# Pathfinder.net
KiCad netlist of a schematic drawn in Altium Designer
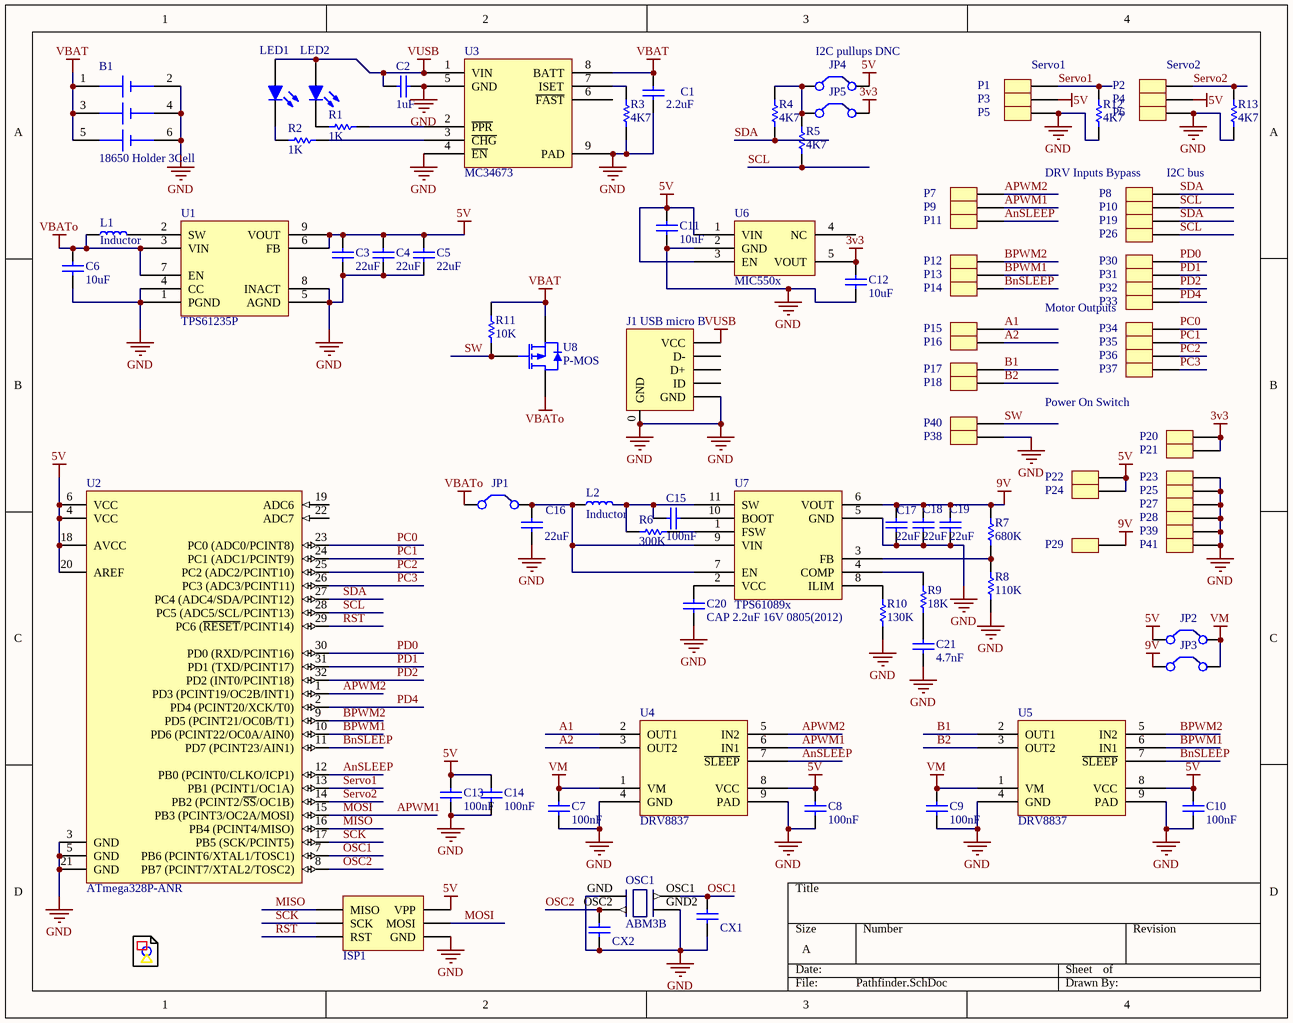
[diagram p0: Pathfinder.SchDoc]

(export (version "E")
  (design (tool "Eeschema 10.0.6"))
  (components
    (comp (ref "*") (value "Logo") (footprint "Zap Cloud") (libsource (lib "DennyLogo") (part "Logo")))
    (comp (ref "B1")
      (value "18650 Holder 3Cell")
      (footprint "18650-3Cell")
      (description "BK-18650-PC6")
      (libsource (lib "Pathfinder_lib") (part "BK18650-3Cell"))
    )
    (comp (ref "C1")
      (value "2.2uF")
      (footprint "CAPC0805(2012)100_L")
      (description "CAP 2.2uF 16V ±10% 0805 (2012 Metric) Thickness 1mm SMD")
      (fields (field (name "TOLERANCE") "Â±10%"))
      (libsource (lib "Altium Content Vault") (part "CAP"))
    )
    (comp (ref "C2")
      (value "1uF")
      (footprint "CAPC0805(2012)100_L")
      (description "CAP 1uF 16V ±20% 0805 (2012 Metric) Thickness 1mm SMD")
      (fields (field (name "TOLERANCE") "Â±20%"))
      (libsource (lib "Altium Content Vault") (part "CAP"))
    )
    (comp (ref "C3")
      (value "22uF")
      (footprint "CAPC0805(2012)100_L")
      (description "CAP 22uF 10V ±20% 0805 (2012 Metric) Thickness 1mm SMD")
      (fields (field (name "TOLERANCE") "Â±20%"))
      (libsource (lib "Altium Content Vault") (part "CAP"))
    )
    (comp (ref "C4")
      (value "22uF")
      (footprint "CAPC0805(2012)100_L")
      (description "CAP 22uF 10V ±20% 0805 (2012 Metric) Thickness 1mm SMD")
      (fields (field (name "TOLERANCE") "Â±20%"))
      (libsource (lib "Altium Content Vault") (part "CAP"))
    )
    (comp (ref "C5")
      (value "22uF")
      (footprint "CAPC0805(2012)100_L")
      (description "CAP 22uF 10V ±20% 0805 (2012 Metric) Thickness 1mm SMD")
      (fields (field (name "TOLERANCE") "Â±20%"))
      (libsource (lib "Altium Content Vault") (part "CAP"))
    )
    (comp (ref "C6")
      (value "10uF")
      (footprint "CAPC0805(2012)145_M")
      (description "CAP 10uF 10V -20% to +80% 0805 (2012 Metric) Thickness 1.45mm SMD")
      (fields (field (name "TOLERANCE") "-20% to +80%"))
      (libsource (lib "Altium Content Vault") (part "CAP"))
    )
    (comp (ref "C7")
      (value "100nF")
      (footprint "CAPC0805(2012)100_M")
      (description "CAP 100nF 10V ±10% 0805 (2012 Metric) Thickness 1mm SMD")
      (fields (field (name "TOLERANCE") "Â±10%"))
      (libsource (lib "Altium Content Vault") (part "CAP"))
    )
    (comp (ref "C8")
      (value "100nF")
      (footprint "CAPC0805(2012)100_M")
      (description "CAP 100nF 10V ±10% 0805 (2012 Metric) Thickness 1mm SMD")
      (fields (field (name "TOLERANCE") "Â±10%"))
      (libsource (lib "Altium Content Vault") (part "CAP"))
    )
    (comp (ref "C9")
      (value "100nF")
      (footprint "CAPC0805(2012)100_M")
      (description "CAP 100nF 10V ±10% 0805 (2012 Metric) Thickness 1mm SMD")
      (fields (field (name "TOLERANCE") "Â±10%"))
      (libsource (lib "Altium Content Vault") (part "CAP"))
    )
    (comp (ref "C10")
      (value "100nF")
      (footprint "CAPC0805(2012)100_M")
      (description "CAP 100nF 10V ±10% 0805 (2012 Metric) Thickness 1mm SMD")
      (fields (field (name "TOLERANCE") "Â±10%"))
      (libsource (lib "Altium Content Vault") (part "CAP"))
    )
    (comp (ref "C11")
      (value "10uF")
      (footprint "CAPC0805(2012)145_M")
      (description "CAP 10uF 10V -20% to +80% 0805 (2012 Metric) Thickness 1.45mm SMD")
      (fields (field (name "TOLERANCE") "-20% to +80%"))
      (libsource (lib "Altium Content Vault") (part "CAP"))
    )
    (comp (ref "C12")
      (value "10uF")
      (footprint "CAPC0805(2012)145_M")
      (description "CAP 10uF 10V -20% to +80% 0805 (2012 Metric) Thickness 1.45mm SMD")
      (fields (field (name "TOLERANCE") "-20% to +80%"))
      (libsource (lib "Altium Content Vault") (part "CAP"))
    )
    (comp (ref "C13")
      (value "100nF")
      (footprint "CAPC0805(2012)100_M")
      (description "CAP 100nF 10V ±10% 0805 (2012 Metric) Thickness 1mm SMD")
      (fields (field (name "TOLERANCE") "Â±10%"))
      (libsource (lib "Altium Content Vault") (part "CAP"))
    )
    (comp (ref "C14")
      (value "100nF")
      (footprint "CAPC0805(2012)100_M")
      (description "CAP 100nF 10V ±10% 0805 (2012 Metric) Thickness 1mm SMD")
      (fields (field (name "TOLERANCE") "Â±10%"))
      (libsource (lib "Altium Content Vault") (part "CAP"))
    )
    (comp (ref "C15")
      (value "100nF")
      (footprint "CAPC0805(2012)100_M")
      (description "CAP 100nF 10V ±10% 0805 (2012 Metric) Thickness 1mm SMD")
      (fields (field (name "TOLERANCE") "Â±10%"))
      (libsource (lib "Altium Content Vault") (part "CAP"))
    )
    (comp (ref "C16")
      (value "22uF")
      (footprint "CAPC0805(2012)100_L")
      (description "CAP 22uF 10V ±20% 0805 (2012 Metric) Thickness 1mm SMD")
      (fields (field (name "TOLERANCE") "Â±20%"))
      (libsource (lib "Altium Content Vault") (part "CAP"))
    )
    (comp (ref "C17")
      (value "22uF")
      (footprint "CAPC0805(2012)100_L")
      (description "CAP 22uF 10V ±20% 0805 (2012 Metric) Thickness 1mm SMD")
      (fields (field (name "TOLERANCE") "Â±20%"))
      (libsource (lib "Altium Content Vault") (part "CAP"))
    )
    (comp (ref "C18")
      (value "22uF")
      (footprint "CAPC0805(2012)100_L")
      (description "CAP 22uF 10V ±20% 0805 (2012 Metric) Thickness 1mm SMD")
      (fields (field (name "TOLERANCE") "Â±20%"))
      (libsource (lib "Altium Content Vault") (part "CAP"))
    )
    (comp (ref "C19")
      (value "22uF")
      (footprint "CAPC0805(2012)100_L")
      (description "CAP 22uF 10V ±20% 0805 (2012 Metric) Thickness 1mm SMD")
      (fields (field (name "TOLERANCE") "Â±20%"))
      (libsource (lib "Altium Content Vault") (part "CAP"))
    )
    (comp (ref "C20")
      (value "CAP 2.2uF 16V 0805(2012)")
      (footprint "CAPC0805(2012)145_L")
      (description "CAP 2.2uF 16V ±10% 0805 (2012 Metric) Thickness 1.45mm SMD")
      (fields (field (name "TOLERANCE") "Â±10%"))
      (libsource (lib "Altium Content Vault") (part "CAP"))
    )
    (comp (ref "C21")
      (value "4.7nF")
      (footprint "CAPC0805(2012)145_N")
      (description "CAP 4.7nF 16V ±1% 0805 (2012 Metric) Thickness 1.45mm SMD")
      (fields (field (name "TOLERANCE") "Â±1%"))
      (libsource (lib "Altium Content Vault") (part "CAP"))
    )
    (comp (ref "CX1")
      (value "CAP 22pF 10V 0603(1608)")
      (footprint "CAPC0603(1608)100_M")
      (description "CAP 22pF 10V ±0.5pF 0603 (1608 Metric) Thickness 1mm SMD")
      (fields (field (name "TOLERANCE") "±0.5pF"))
      (libsource (lib "Altium Content Vault") (part "CMP-1035-00798-1"))
    )
    (comp (ref "CX2")
      (value "CAP 22pF 10V 0603(1608)")
      (footprint "CAPC0603(1608)100_M")
      (description "CAP 22pF 10V ±0.5pF 0603 (1608 Metric) Thickness 1mm SMD")
      (fields (field (name "TOLERANCE") "±0.5pF"))
      (libsource (lib "Altium Content Vault") (part "CMP-1035-00798-1"))
    )
    (comp (ref "ISP1")
      (value "AVRISP")
      (footprint "2x3 100mil Header")
      (description "AVR ISP connection")
      (libsource (lib "Denny") (part "AVRISP"))
    )
    (comp (ref "J1")
      (value "USB micro B")
      (footprint "USB Micro SMD")
      (description "Micro USB connector")
      (libsource (lib "SolarCar") (part "Micro-USB"))
    )
    (comp (ref "JP1")
      (value "SolderJumper")
      (footprint "bridge")
      (description "Solder Configuration Jumper")
      (fields (field (name "PUBLISHER") "Altium Limited"))
      (libsource (lib "SolarCar") (part "SolderJumper"))
    )
    (comp (ref "JP2")
      (value "SolderJumper")
      (footprint "bridge")
      (description "Solder Configuration Jumper")
      (fields (field (name "PUBLISHER") "Altium Limited"))
      (libsource (lib "SolarCar") (part "SolderJumper"))
    )
    (comp (ref "JP3")
      (value "SolderJumper")
      (footprint "bridge")
      (description "Solder Configuration Jumper")
      (fields (field (name "PUBLISHER") "Altium Limited"))
      (libsource (lib "SolarCar") (part "SolderJumper"))
    )
    (comp (ref "JP4")
      (value "SolderJumper")
      (footprint "bridge")
      (description "Solder Configuration Jumper")
      (fields (field (name "PUBLISHER") "Altium Limited"))
      (libsource (lib "SolarCar") (part "SolderJumper"))
    )
    (comp (ref "JP5")
      (value "SolderJumper")
      (footprint "bridge")
      (description "Solder Configuration Jumper")
      (fields (field (name "PUBLISHER") "Altium Limited"))
      (libsource (lib "SolarCar") (part "SolderJumper"))
    )
    (comp (ref "L1")
      (value "Inductor")
      (footprint "XAL7030-102ME")
      (description "Generic Inductor")
      (libsource (lib "Pathfinder_lib") (part "Inductor"))
    )
    (comp (ref "L2")
      (value "Inductor")
      (footprint "CDMC8D28NP-1R8MC")
      (description "Generic Inductor")
      (libsource (lib "Pathfinder_lib") (part "Inductor"))
    )
    (comp (ref "LED1")
      (value "LED2")
      (footprint "LED0805")
      (description "Typical RED, GREEN, YELLOW, AMBER GaAs LED")
      (fields (field (name "PUBLISHER") "Altium Limited"))
      (libsource (lib "SolarCar") (part "LED2"))
    )
    (comp (ref "LED2")
      (value "LED2")
      (footprint "LED0805")
      (description "Typical RED, GREEN, YELLOW, AMBER GaAs LED")
      (fields (field (name "PUBLISHER") "Altium Limited"))
      (libsource (lib "SolarCar") (part "LED2"))
    )
    (comp (ref "OSC1") (value "ABM3B") (footprint "ABM3B") (libsource (lib "SolarCar") (part "ABM3B")))
    (comp (ref "P1") (value "SV1") (footprint "Pin 100mil") (libsource (lib "SolarCar") (part "1-Pin")))
    (comp (ref "P2") (value "SV2") (footprint "Pin 100mil") (libsource (lib "SolarCar") (part "1-Pin")))
    (comp (ref "P3") (value "5V") (footprint "Pin 100mil") (libsource (lib "SolarCar") (part "1-Pin")))
    (comp (ref "P4") (value "5V") (footprint "Pin 100mil") (libsource (lib "SolarCar") (part "1-Pin")))
    (comp (ref "P5") (value "GND") (footprint "Pin 100mil") (libsource (lib "SolarCar") (part "1-Pin")))
    (comp (ref "P6") (value "GND") (footprint "Pin 100mil") (libsource (lib "SolarCar") (part "1-Pin")))
    (comp (ref "P7") (value "Ain2") (footprint "Pin 100mil") (libsource (lib "SolarCar") (part "1-Pin")))
    (comp (ref "P8") (value "SDA") (footprint "Pin 100mil") (libsource (lib "SolarCar") (part "1-Pin")))
    (comp (ref "P9") (value "Ain1") (footprint "Pin 100mil") (libsource (lib "SolarCar") (part "1-Pin")))
    (comp (ref "P10") (value "SCL") (footprint "Pin 100mil") (libsource (lib "SolarCar") (part "1-Pin")))
    (comp (ref "P11") (value "ASLP") (footprint "Pin 100mil") (libsource (lib "SolarCar") (part "1-Pin")))
    (comp (ref "P12") (value "Bin2") (footprint "Pin 100mil") (libsource (lib "SolarCar") (part "1-Pin")))
    (comp (ref "P13") (value "Bin1") (footprint "Pin 100mil") (libsource (lib "SolarCar") (part "1-Pin")))
    (comp (ref "P14") (value "BSLP") (footprint "Pin 100mil") (libsource (lib "SolarCar") (part "1-Pin")))
    (comp (ref "P15") (value "AO1") (footprint "Pin 100mil") (libsource (lib "SolarCar") (part "1-Pin")))
    (comp (ref "P16") (value "AO2") (footprint "Pin 100mil") (libsource (lib "SolarCar") (part "1-Pin")))
    (comp (ref "P17") (value "BO1") (footprint "Pin 100mil") (libsource (lib "SolarCar") (part "1-Pin")))
    (comp (ref "P18") (value "BO2") (footprint "Pin 100mil") (libsource (lib "SolarCar") (part "1-Pin")))
    (comp (ref "P19") (value "SDA") (footprint "Pin 100mil") (libsource (lib "SolarCar") (part "1-Pin")))
    (comp (ref "P20") (value "3v3") (footprint "Pin 100mil") (libsource (lib "SolarCar") (part "1-Pin")))
    (comp (ref "P21") (value "3v3") (footprint "Pin 100mil") (libsource (lib "SolarCar") (part "1-Pin")))
    (comp (ref "P22") (value "5V") (footprint "Pin 100mil") (libsource (lib "SolarCar") (part "1-Pin")))
    (comp (ref "P23") (value "GND") (footprint "Pin 100mil") (libsource (lib "SolarCar") (part "1-Pin")))
    (comp (ref "P24") (value "5V") (footprint "Pin 100mil") (libsource (lib "SolarCar") (part "1-Pin")))
    (comp (ref "P25") (value "GND") (footprint "Pin 100mil") (libsource (lib "SolarCar") (part "1-Pin")))
    (comp (ref "P26") (value "SCL") (footprint "Pin 100mil") (libsource (lib "SolarCar") (part "1-Pin")))
    (comp (ref "P27") (value "GND") (footprint "Pin 100mil") (libsource (lib "SolarCar") (part "1-Pin")))
    (comp (ref "P28") (value "GND") (footprint "Pin 100mil") (libsource (lib "SolarCar") (part "1-Pin")))
    (comp (ref "P29") (value "9V") (footprint "Pin 100mil") (libsource (lib "SolarCar") (part "1-Pin")))
    (comp (ref "P30") (value "PD0") (footprint "Pin 100mil") (libsource (lib "SolarCar") (part "1-Pin")))
    (comp (ref "P31") (value "PD1") (footprint "Pin 100mil") (libsource (lib "SolarCar") (part "1-Pin")))
    (comp (ref "P32") (value "PD2") (footprint "Pin 100mil") (libsource (lib "SolarCar") (part "1-Pin")))
    (comp (ref "P33") (value "PD4") (footprint "Pin 100mil") (libsource (lib "SolarCar") (part "1-Pin")))
    (comp (ref "P34") (value "PC0") (footprint "Pin 100mil") (libsource (lib "SolarCar") (part "1-Pin")))
    (comp (ref "P35") (value "PC1") (footprint "Pin 100mil") (libsource (lib "SolarCar") (part "1-Pin")))
    (comp (ref "P36") (value "PC2") (footprint "Pin 100mil") (libsource (lib "SolarCar") (part "1-Pin")))
    (comp (ref "P37") (value "PC3") (footprint "Pin 100mil") (libsource (lib "SolarCar") (part "1-Pin")))
    (comp (ref "P38") (value "SDA") (footprint "Pin 100mil") (libsource (lib "SolarCar") (part "1-Pin")))
    (comp (ref "P39") (value "GND") (footprint "Pin 100mil") (libsource (lib "SolarCar") (part "1-Pin")))
    (comp (ref "P40") (value "SDA") (footprint "Pin 100mil") (libsource (lib "SolarCar") (part "1-Pin")))
    (comp (ref "P41") (value "GND") (footprint "Pin 100mil") (libsource (lib "SolarCar") (part "1-Pin")))
    (comp (ref "R1")
      (value "1K")
      (footprint "RESC0805(2012)_N")
      (description "1K 0.125W 5% 0805 (2012 Metric)  SMD")
      (fields (field (name "POWER") "0.125 W") (field (name "TOLERANCE") "5 %"))
      (libsource (lib "Altium Content Vault") (part "RES"))
    )
    (comp (ref "R2")
      (value "1K")
      (footprint "RESC0805(2012)_N")
      (description "1K 0.125W 5% 0805 (2012 Metric)  SMD")
      (fields (field (name "POWER") "0.125 W") (field (name "TOLERANCE") "5 %"))
      (libsource (lib "Altium Content Vault") (part "RES"))
    )
    (comp (ref "R3")
      (value "4K7")
      (footprint "RESC0805(2012)_N")
      (description "4K7 0.125W 5% 0805 (2012 Metric)  SMD")
      (fields (field (name "POWER") "0.125 W") (field (name "TOLERANCE") "5 %"))
      (libsource (lib "Altium Content Vault") (part "RES"))
    )
    (comp (ref "R4")
      (value "4K7")
      (footprint "RESC0805(2012)_N")
      (description "4K7 0.125W 5% 0805 (2012 Metric)  SMD")
      (fields (field (name "POWER") "0.125 W") (field (name "TOLERANCE") "5 %"))
      (libsource (lib "Altium Content Vault") (part "RES"))
    )
    (comp (ref "R5")
      (value "4K7")
      (footprint "RESC0805(2012)_N")
      (description "4K7 0.125W 5% 0805 (2012 Metric)  SMD")
      (fields (field (name "POWER") "0.125 W") (field (name "TOLERANCE") "5 %"))
      (libsource (lib "Altium Content Vault") (part "RES"))
    )
    (comp (ref "R6")
      (value "300K")
      (footprint "RESC0805(2012)_M")
      (description "300K 0.125W 5% 0805 (2012 Metric)  SMD")
      (fields (field (name "TOLERANCE") "5 %") (field (name "POWER") "0.125 W"))
      (libsource (lib "Altium Content Vault") (part "RES"))
    )
    (comp (ref "R7")
      (value "680K")
      (footprint "RESC0805(2012)_M")
      (description "680K 0.125W 5% 0805 (2012 Metric)  SMD")
      (fields (field (name "POWER") "0.125 W") (field (name "TOLERANCE") "5 %"))
      (libsource (lib "Altium Content Vault") (part "RES"))
    )
    (comp (ref "R8")
      (value "110K")
      (footprint "RESC0805(2012)_M")
      (description "110K 0.125W 5% 0805 (2012 Metric)  SMD")
      (fields (field (name "TOLERANCE") "5 %") (field (name "POWER") "0.125 W"))
      (libsource (lib "Altium Content Vault") (part "RES"))
    )
    (comp (ref "R9")
      (value "18K")
      (footprint "RESC0805(2012)_M")
      (description "18K 0.125W 5% 0805 (2012 Metric)  SMD")
      (fields (field (name "POWER") "0.125 W") (field (name "TOLERANCE") "5 %"))
      (libsource (lib "Altium Content Vault") (part "RES"))
    )
    (comp (ref "R10")
      (value "130K")
      (footprint "RESC0805(2012)_N")
      (description "130K 0.125W 5% 0805 (2012 Metric)  SMD")
      (fields (field (name "TOLERANCE") "5 %") (field (name "POWER") "0.125 W"))
      (libsource (lib "Altium Content Vault") (part "RES"))
    )
    (comp (ref "R11")
      (value "10K")
      (footprint "RESC0603(1608)_N")
      (description "10K 0.1W 5% 0603 (1608 Metric)  SMD")
      (fields (field (name "TOLERANCE") "5 %") (field (name "POWER") "0.1 W"))
      (libsource (lib "Altium Content Vault") (part "RES"))
    )
    (comp (ref "R12")
      (value "4K7")
      (footprint "RESC0805(2012)_N")
      (description "4K7 0.125W 5% 0805 (2012 Metric)  SMD")
      (fields (field (name "POWER") "0.125 W") (field (name "TOLERANCE") "5 %"))
      (libsource (lib "Altium Content Vault") (part "RES"))
    )
    (comp (ref "R13")
      (value "4K7")
      (footprint "RESC0805(2012)_N")
      (description "4K7 0.125W 5% 0805 (2012 Metric)  SMD")
      (fields (field (name "POWER") "0.125 W") (field (name "TOLERANCE") "5 %"))
      (libsource (lib "Altium Content Vault") (part "RES"))
    )
    (comp (ref "U1")
      (value "TPS61235P")
      (footprint "VQFN-HR-TPS61235PRWLR")
      (description "8-A Valley Current Synchronous Boost Converter")
      (libsource (lib "Pathfinder_lib") (part "TPS61235P"))
    )
    (comp (ref "U2")
      (value "ATmega328P-ANR")
      (footprint "32A_M")
      (libsource (lib "Altium Content Vault") (part "CMP-0095-00621-1"))
    )
    (comp (ref "U3")
      (value "MC34673")
      (footprint "UDFN-8 2 x 3 x 0.65")
      (description "1.2A Charger  for Single-cell Li-Ion Batteries")
      (libsource (lib "Pathfinder_lib") (part "MC34673"))
    )
    (comp (ref "U4")
      (value "DRV8837")
      (footprint "WSON-8")
      (description "Low-Voltage H-Bridge Driver")
      (libsource (lib "Pathfinder_lib") (part "DRV8837"))
    )
    (comp (ref "U5")
      (value "DRV8837")
      (footprint "WSON-8")
      (description "Low-Voltage H-Bridge Driver")
      (libsource (lib "Pathfinder_lib") (part "DRV8837"))
    )
    (comp (ref "U6")
      (value "MIC550x")
      (footprint "SOT-23-5")
      (description "MIC550x Regulator")
      (libsource (lib "Denny") (part "MIC550x"))
    )
    (comp (ref "U7")
      (value "TPS61089x")
      (footprint "VQFN-11 2 x 2.5")
      (description "12.6-V, 7-A Fully-Integrated Synchronous Boost Converter")
      (libsource (lib "Pathfinder_lib") (part "TPS61089x"))
    )
    (comp (ref "U8")
      (value "P-MOS")
      (footprint "SOIC-8-MOSFET")
      (description "SI4403CDY-T1")
      (libsource (lib "Pathfinder_lib") (part "SI4403CDY-T1"))
    )
  )
  (nets
    (net (code "1") (name "/A1") (class "Default")
      (node (ref "P15") (pin "0") (pinfunction "0_0") (pintype "passive"))
      (node (ref "U4") (pin "2") (pinfunction "OUT1_2") (pintype "passive"))
    )
    (net (code "2") (name "/A2") (class "Default")
      (node (ref "P16") (pin "0") (pinfunction "0_0") (pintype "passive"))
      (node (ref "U4") (pin "3") (pinfunction "OUT2_3") (pintype "passive"))
    )
    (net (code "3") (name "/APWM1") (class "Default")
      (node (ref "ISP1") (pin "4") (pinfunction "MOSI_4") (pintype "passive"))
      (node (ref "P9") (pin "0") (pinfunction "0_0") (pintype "passive"))
      (node (ref "U2") (pin "15") (pinfunction "PB3_(PCINT3/OC2A/MOSI)_15") (pintype "bidirectional"))
      (node (ref "U4") (pin "6") (pinfunction "IN1_6") (pintype "passive"))
    )
    (net (code "4") (name "/APWM2") (class "Default")
      (node (ref "P7") (pin "0") (pinfunction "0_0") (pintype "passive"))
      (node (ref "U2") (pin "1") (pinfunction "PD3_(PCINT19/OC2B/INT1)_1") (pintype "bidirectional"))
      (node (ref "U4") (pin "5") (pinfunction "IN2_5") (pintype "passive"))
    )
    (net (code "5") (name "/AnSLEEP") (class "Default")
      (node (ref "P11") (pin "0") (pinfunction "0_0") (pintype "passive"))
      (node (ref "U2") (pin "12") (pinfunction "PB0_(PCINT0/CLKO/ICP1)_12") (pintype "bidirectional"))
      (node (ref "U4") (pin "7") (pinfunction "~{SLEEP}_7") (pintype "passive"))
    )
    (net (code "6") (name "/B1") (class "Default")
      (node (ref "P17") (pin "0") (pinfunction "0_0") (pintype "passive"))
      (node (ref "U5") (pin "2") (pinfunction "OUT1_2") (pintype "passive"))
    )
    (net (code "7") (name "/B2") (class "Default")
      (node (ref "P18") (pin "0") (pinfunction "0_0") (pintype "passive"))
      (node (ref "U5") (pin "3") (pinfunction "OUT2_3") (pintype "passive"))
    )
    (net (code "8") (name "/BPWM1") (class "Default")
      (node (ref "P13") (pin "0") (pinfunction "0_0") (pintype "passive"))
      (node (ref "U2") (pin "10") (pinfunction "PD6_(PCINT22/OC0A/AIN0)_10") (pintype "bidirectional"))
      (node (ref "U5") (pin "6") (pinfunction "IN1_6") (pintype "passive"))
    )
    (net (code "9") (name "/BPWM2") (class "Default")
      (node (ref "P12") (pin "0") (pinfunction "0_0") (pintype "passive"))
      (node (ref "U2") (pin "9") (pinfunction "PD5_(PCINT21/OC0B/T1)_9") (pintype "bidirectional"))
      (node (ref "U5") (pin "5") (pinfunction "IN2_5") (pintype "passive"))
    )
    (net (code "10") (name "/BnSLEEP") (class "Default")
      (node (ref "P14") (pin "0") (pinfunction "0_0") (pintype "passive"))
      (node (ref "U2") (pin "11") (pinfunction "PD7_(PCINT23/AIN1)_11") (pintype "bidirectional"))
      (node (ref "U5") (pin "7") (pinfunction "~{SLEEP}_7") (pintype "passive"))
    )
    (net (code "11") (name "/MISO") (class "Default")
      (node (ref "ISP1") (pin "1") (pinfunction "MISO_1") (pintype "passive"))
      (node (ref "U2") (pin "16") (pinfunction "PB4_(PCINT4/MISO)_16") (pintype "bidirectional"))
    )
    (net (code "12") (name "/OSC1") (class "Default")
      (node (ref "CX1") (pin "2") (pinfunction "2_2") (pintype "passive"))
      (node (ref "OSC1") (pin "OSC1") (pinfunction "OSC1_OSC1") (pintype "output"))
      (node (ref "U2") (pin "7") (pinfunction "PB6_(PCINT6/XTAL1/TOSC1)_7") (pintype "bidirectional"))
    )
    (net (code "13") (name "/OSC2") (class "Default")
      (node (ref "CX2") (pin "2") (pinfunction "2_2") (pintype "passive"))
      (node (ref "OSC1") (pin "OSC2") (pinfunction "OSC2_OSC2") (pintype "output"))
      (node (ref "U2") (pin "8") (pinfunction "PB7_(PCINT7/XTAL2/TOSC2)_8") (pintype "bidirectional"))
    )
    (net (code "14") (name "/PC0") (class "Default")
      (node (ref "P34") (pin "0") (pinfunction "0_0") (pintype "passive"))
      (node (ref "U2") (pin "23") (pinfunction "PC0_(ADC0/PCINT8)_23") (pintype "bidirectional"))
    )
    (net (code "15") (name "/PC1") (class "Default")
      (node (ref "P35") (pin "0") (pinfunction "0_0") (pintype "passive"))
      (node (ref "U2") (pin "24") (pinfunction "PC1_(ADC1/PCINT9)_24") (pintype "bidirectional"))
    )
    (net (code "16") (name "/PC2") (class "Default")
      (node (ref "P36") (pin "0") (pinfunction "0_0") (pintype "passive"))
      (node (ref "U2") (pin "25") (pinfunction "PC2_(ADC2/PCINT10)_25") (pintype "bidirectional"))
    )
    (net (code "17") (name "/PC3") (class "Default")
      (node (ref "P37") (pin "0") (pinfunction "0_0") (pintype "passive"))
      (node (ref "U2") (pin "26") (pinfunction "PC3_(ADC3/PCINT11)_26") (pintype "bidirectional"))
    )
    (net (code "18") (name "/PD0") (class "Default")
      (node (ref "P30") (pin "0") (pinfunction "0_0") (pintype "passive"))
      (node (ref "U2") (pin "30") (pinfunction "PD0_(RXD/PCINT16)_30") (pintype "bidirectional"))
    )
    (net (code "19") (name "/PD1") (class "Default")
      (node (ref "P31") (pin "0") (pinfunction "0_0") (pintype "passive"))
      (node (ref "U2") (pin "31") (pinfunction "PD1_(TXD/PCINT17)_31") (pintype "bidirectional"))
    )
    (net (code "20") (name "/PD2") (class "Default")
      (node (ref "P32") (pin "0") (pinfunction "0_0") (pintype "passive"))
      (node (ref "U2") (pin "32") (pinfunction "PD2_(INT0/PCINT18)_32") (pintype "bidirectional"))
    )
    (net (code "21") (name "/PD4") (class "Default")
      (node (ref "P33") (pin "0") (pinfunction "0_0") (pintype "passive"))
      (node (ref "U2") (pin "2") (pinfunction "PD4_(PCINT20/XCK/T0)_2") (pintype "bidirectional"))
    )
    (net (code "22") (name "/RST") (class "Default")
      (node (ref "ISP1") (pin "5") (pinfunction "RST_5") (pintype "passive"))
      (node (ref "U2") (pin "29") (pinfunction "PC6_(~{RESET}/PCINT14)_29") (pintype "bidirectional"))
    )
    (net (code "23") (name "/SCK") (class "Default")
      (node (ref "ISP1") (pin "3") (pinfunction "SCK_3") (pintype "passive"))
      (node (ref "U2") (pin "17") (pinfunction "PB5_(SCK/PCINT5)_17") (pintype "bidirectional"))
    )
    (net (code "24") (name "/SCL") (class "Default")
      (node (ref "P10") (pin "0") (pinfunction "0_0") (pintype "passive"))
      (node (ref "P26") (pin "0") (pinfunction "0_0") (pintype "passive"))
      (node (ref "R5") (pin "1") (pinfunction "1_1") (pintype "passive"))
      (node (ref "U2") (pin "28") (pinfunction "PC5_(ADC5/SCL/PCINT13)_28") (pintype "bidirectional"))
    )
    (net (code "25") (name "/SDA") (class "Default")
      (node (ref "P19") (pin "0") (pinfunction "0_0") (pintype "passive"))
      (node (ref "P8") (pin "0") (pinfunction "0_0") (pintype "passive"))
      (node (ref "R4") (pin "1") (pinfunction "1_1") (pintype "passive"))
      (node (ref "U2") (pin "27") (pinfunction "PC4_(ADC4/SDA/PCINT12)_27") (pintype "bidirectional"))
    )
    (net (code "26") (name "/SW") (class "Default")
      (node (ref "P40") (pin "0") (pinfunction "0_0") (pintype "passive"))
      (node (ref "R11") (pin "1") (pinfunction "1_1") (pintype "passive"))
      (node (ref "U8") (pin "2") (pinfunction "G_2") (pintype "passive"))
    )
    (net (code "27") (name "/Servo1") (class "Default")
      (node (ref "P1") (pin "0") (pinfunction "0_0") (pintype "passive"))
      (node (ref "R12") (pin "2") (pinfunction "2_2") (pintype "passive"))
      (node (ref "U2") (pin "13") (pinfunction "PB1_(PCINT1/OC1A)_13") (pintype "bidirectional"))
    )
    (net (code "28") (name "/Servo2") (class "Default")
      (node (ref "P2") (pin "0") (pinfunction "0_0") (pintype "passive"))
      (node (ref "R13") (pin "2") (pinfunction "2_2") (pintype "passive"))
      (node (ref "U2") (pin "14") (pinfunction "PB2_(PCINT2/~{SS}/OC1B)_14") (pintype "bidirectional"))
    )
    (net (code "29") (name "3v3") (class "Default")
      (node (ref "C12") (pin "2") (pinfunction "2_2") (pintype "passive"))
      (node (ref "JP5") (pin "2") (pinfunction "C2_2") (pintype "passive"))
      (node (ref "P20") (pin "0") (pinfunction "0_0") (pintype "passive"))
      (node (ref "P21") (pin "0") (pinfunction "0_0") (pintype "passive"))
      (node (ref "U6") (pin "5") (pinfunction "VOUT_5") (pintype "passive"))
    )
    (net (code "30") (name "5V") (class "Default")
      (node (ref "C10") (pin "2") (pinfunction "2_2") (pintype "passive"))
      (node (ref "C11") (pin "2") (pinfunction "2_2") (pintype "passive"))
      (node (ref "C13") (pin "2") (pinfunction "2_2") (pintype "passive"))
      (node (ref "C14") (pin "2") (pinfunction "2_2") (pintype "passive"))
      (node (ref "C3") (pin "2") (pinfunction "2_2") (pintype "passive"))
      (node (ref "C4") (pin "2") (pinfunction "2_2") (pintype "passive"))
      (node (ref "C5") (pin "2") (pinfunction "2_2") (pintype "passive"))
      (node (ref "C8") (pin "2") (pinfunction "2_2") (pintype "passive"))
      (node (ref "ISP1") (pin "2") (pinfunction "VPP_2") (pintype "passive"))
      (node (ref "JP2") (pin "1") (pinfunction "C1_1") (pintype "passive"))
      (node (ref "JP4") (pin "2") (pinfunction "C2_2") (pintype "passive"))
      (node (ref "P22") (pin "0") (pinfunction "0_0") (pintype "passive"))
      (node (ref "P24") (pin "0") (pinfunction "0_0") (pintype "passive"))
      (node (ref "P3") (pin "0") (pinfunction "0_0") (pintype "passive"))
      (node (ref "P4") (pin "0") (pinfunction "0_0") (pintype "passive"))
      (node (ref "U1") (pin "6") (pinfunction "FB_6") (pintype "passive"))
      (node (ref "U1") (pin "9") (pinfunction "VOUT_9") (pintype "passive"))
      (node (ref "U2") (pin "18") (pinfunction "AVCC_18") (pintype "power_in"))
      (node (ref "U2") (pin "20") (pinfunction "AREF_20") (pintype "passive"))
      (node (ref "U2") (pin "4") (pinfunction "VCC_4") (pintype "power_in"))
      (node (ref "U2") (pin "6") (pinfunction "VCC_6") (pintype "power_in"))
      (node (ref "U4") (pin "8") (pinfunction "VCC_8") (pintype "passive"))
      (node (ref "U5") (pin "8") (pinfunction "VCC_8") (pintype "passive"))
      (node (ref "U6") (pin "1") (pinfunction "VIN_1") (pintype "passive"))
      (node (ref "U6") (pin "3") (pinfunction "EN_3") (pintype "passive"))
    )
    (net (code "31") (name "9V") (class "Default")
      (node (ref "C17") (pin "2") (pinfunction "2_2") (pintype "passive"))
      (node (ref "C18") (pin "2") (pinfunction "2_2") (pintype "passive"))
      (node (ref "C19") (pin "2") (pinfunction "2_2") (pintype "passive"))
      (node (ref "JP3") (pin "1") (pinfunction "C1_1") (pintype "passive"))
      (node (ref "P29") (pin "0") (pinfunction "0_0") (pintype "passive"))
      (node (ref "R7") (pin "2") (pinfunction "2_2") (pintype "passive"))
      (node (ref "U7") (pin "6") (pinfunction "VOUT_6") (pintype "passive"))
    )
    (net (code "32") (name "GND") (class "Default")
      (node (ref "B1") (pin "2") (pinfunction "2_2") (pintype "passive"))
      (node (ref "B1") (pin "4") (pinfunction "4_4") (pintype "passive"))
      (node (ref "B1") (pin "6") (pinfunction "6_6") (pintype "passive"))
      (node (ref "C1") (pin "1") (pinfunction "1_1") (pintype "passive"))
      (node (ref "C10") (pin "1") (pinfunction "1_1") (pintype "passive"))
      (node (ref "C11") (pin "1") (pinfunction "1_1") (pintype "passive"))
      (node (ref "C12") (pin "1") (pinfunction "1_1") (pintype "passive"))
      (node (ref "C13") (pin "1") (pinfunction "1_1") (pintype "passive"))
      (node (ref "C14") (pin "1") (pinfunction "1_1") (pintype "passive"))
      (node (ref "C16") (pin "1") (pinfunction "1_1") (pintype "passive"))
      (node (ref "C17") (pin "1") (pinfunction "1_1") (pintype "passive"))
      (node (ref "C18") (pin "1") (pinfunction "1_1") (pintype "passive"))
      (node (ref "C19") (pin "1") (pinfunction "1_1") (pintype "passive"))
      (node (ref "C2") (pin "1") (pinfunction "1_1") (pintype "passive"))
      (node (ref "C20") (pin "1") (pinfunction "1_1") (pintype "passive"))
      (node (ref "C21") (pin "1") (pinfunction "1_1") (pintype "passive"))
      (node (ref "C3") (pin "1") (pinfunction "1_1") (pintype "passive"))
      (node (ref "C4") (pin "1") (pinfunction "1_1") (pintype "passive"))
      (node (ref "C5") (pin "1") (pinfunction "1_1") (pintype "passive"))
      (node (ref "C6") (pin "1") (pinfunction "1_1") (pintype "passive"))
      (node (ref "C7") (pin "1") (pinfunction "1_1") (pintype "passive"))
      (node (ref "C8") (pin "1") (pinfunction "1_1") (pintype "passive"))
      (node (ref "C9") (pin "1") (pinfunction "1_1") (pintype "passive"))
      (node (ref "CX1") (pin "1") (pinfunction "1_1") (pintype "passive"))
      (node (ref "CX2") (pin "1") (pinfunction "1_1") (pintype "passive"))
      (node (ref "ISP1") (pin "6") (pinfunction "GND_6") (pintype "passive"))
      (node (ref "J1") (pin "0") (pinfunction "GND_0") (pintype "passive"))
      (node (ref "J1") (pin "5") (pinfunction "GND_5") (pintype "passive"))
      (node (ref "OSC1") (pin "GND") (pinfunction "GND_GND") (pintype "power_in"))
      (node (ref "OSC1") (pin "GND2") (pinfunction "GND_GND2") (pintype "power_in"))
      (node (ref "P23") (pin "0") (pinfunction "0_0") (pintype "passive"))
      (node (ref "P25") (pin "0") (pinfunction "0_0") (pintype "passive"))
      (node (ref "P27") (pin "0") (pinfunction "0_0") (pintype "passive"))
      (node (ref "P28") (pin "0") (pinfunction "0_0") (pintype "passive"))
      (node (ref "P38") (pin "0") (pinfunction "0_0") (pintype "passive"))
      (node (ref "P39") (pin "0") (pinfunction "0_0") (pintype "passive"))
      (node (ref "P41") (pin "0") (pinfunction "0_0") (pintype "passive"))
      (node (ref "P5") (pin "0") (pinfunction "0_0") (pintype "passive"))
      (node (ref "P6") (pin "0") (pinfunction "0_0") (pintype "passive"))
      (node (ref "R10") (pin "1") (pinfunction "1_1") (pintype "passive"))
      (node (ref "R12") (pin "1") (pinfunction "1_1") (pintype "passive"))
      (node (ref "R13") (pin "1") (pinfunction "1_1") (pintype "passive"))
      (node (ref "R3") (pin "1") (pinfunction "1_1") (pintype "passive"))
      (node (ref "R8") (pin "1") (pinfunction "1_1") (pintype "passive"))
      (node (ref "U1") (pin "1") (pinfunction "PGND_1") (pintype "passive"))
      (node (ref "U1") (pin "4") (pinfunction "CC_4") (pintype "passive"))
      (node (ref "U1") (pin "5") (pinfunction "AGND_5") (pintype "passive"))
      (node (ref "U1") (pin "8") (pinfunction "INACT_8") (pintype "passive"))
      (node (ref "U2") (pin "21") (pinfunction "GND_21") (pintype "power_in"))
      (node (ref "U2") (pin "3") (pinfunction "GND_3") (pintype "power_in"))
      (node (ref "U2") (pin "5") (pinfunction "GND_5") (pintype "power_in"))
      (node (ref "U3") (pin "4") (pinfunction "~{EN}_4") (pintype "passive"))
      (node (ref "U3") (pin "5") (pinfunction "GND_5") (pintype "passive"))
      (node (ref "U3") (pin "9") (pinfunction "PAD_9") (pintype "passive"))
      (node (ref "U4") (pin "4") (pinfunction "GND_4") (pintype "passive"))
      (node (ref "U4") (pin "9") (pinfunction "PAD_9") (pintype "passive"))
      (node (ref "U5") (pin "4") (pinfunction "GND_4") (pintype "passive"))
      (node (ref "U5") (pin "9") (pinfunction "PAD_9") (pintype "passive"))
      (node (ref "U6") (pin "2") (pinfunction "GND_2") (pintype "passive"))
      (node (ref "U7") (pin "5") (pinfunction "GND_5") (pintype "passive"))
    )
    (net (code "33") (name "Net-(C21-Pad2)") (class "Default")
      (node (ref "C21") (pin "2") (pinfunction "2_2") (pintype "passive"))
      (node (ref "R9") (pin "1") (pinfunction "1_1") (pintype "passive"))
    )
    (net (code "34") (name "Net-(JP1-C2)") (class "Default")
      (node (ref "C16") (pin "2") (pinfunction "2_2") (pintype "passive"))
      (node (ref "JP1") (pin "2") (pinfunction "C2_2") (pintype "passive"))
      (node (ref "L2") (pin "1") (pinfunction "1_1") (pintype "passive"))
      (node (ref "U7") (pin "7") (pinfunction "EN_7") (pintype "passive"))
      (node (ref "U7") (pin "9") (pinfunction "VIN_9") (pintype "passive"))
    )
    (net (code "35") (name "Net-(JP4-C1)") (class "Default")
      (node (ref "JP4") (pin "1") (pinfunction "C1_1") (pintype "passive"))
      (node (ref "JP5") (pin "1") (pinfunction "C1_1") (pintype "passive"))
      (node (ref "R4") (pin "2") (pinfunction "2_2") (pintype "passive"))
      (node (ref "R5") (pin "2") (pinfunction "2_2") (pintype "passive"))
    )
    (net (code "36") (name "Net-(LED1-K)") (class "Default")
      (node (ref "LED1") (pin "2") (pinfunction "K_2") (pintype "passive"))
      (node (ref "R2") (pin "2") (pinfunction "2_2") (pintype "passive"))
    )
    (net (code "37") (name "Net-(LED2-K)") (class "Default")
      (node (ref "LED2") (pin "2") (pinfunction "K_2") (pintype "passive"))
      (node (ref "R1") (pin "2") (pinfunction "2_2") (pintype "passive"))
    )
    (net (code "38") (name "Net-(U1-SW)") (class "Default")
      (node (ref "L1") (pin "2") (pinfunction "2_2") (pintype "passive"))
      (node (ref "U1") (pin "2") (pinfunction "SW_2") (pintype "passive"))
    )
    (net (code "39") (name "Net-(U3-ISET)") (class "Default")
      (node (ref "R3") (pin "2") (pinfunction "2_2") (pintype "passive"))
      (node (ref "U3") (pin "7") (pinfunction "ISET_7") (pintype "passive"))
    )
    (net (code "40") (name "Net-(U3-~{CHG})") (class "Default")
      (node (ref "R2") (pin "1") (pinfunction "1_1") (pintype "passive"))
      (node (ref "U3") (pin "3") (pinfunction "~{CHG}_3") (pintype "passive"))
    )
    (net (code "41") (name "Net-(U3-~{PPR})") (class "Default")
      (node (ref "R1") (pin "1") (pinfunction "1_1") (pintype "passive"))
      (node (ref "U3") (pin "2") (pinfunction "~{PPR}_2") (pintype "passive"))
    )
    (net (code "42") (name "Net-(U7-BOOT)") (class "Default")
      (node (ref "C15") (pin "1") (pinfunction "1_1") (pintype "passive"))
      (node (ref "U7") (pin "10") (pinfunction "BOOT_10") (pintype "passive"))
    )
    (net (code "43") (name "Net-(U7-COMP)") (class "Default")
      (node (ref "R9") (pin "2") (pinfunction "2_2") (pintype "passive"))
      (node (ref "U7") (pin "4") (pinfunction "COMP_4") (pintype "passive"))
    )
    (net (code "44") (name "Net-(U7-FB)") (class "Default")
      (node (ref "R7") (pin "1") (pinfunction "1_1") (pintype "passive"))
      (node (ref "R8") (pin "2") (pinfunction "2_2") (pintype "passive"))
      (node (ref "U7") (pin "3") (pinfunction "FB_3") (pintype "passive"))
    )
    (net (code "45") (name "Net-(U7-FSW)") (class "Default")
      (node (ref "R6") (pin "1") (pinfunction "1_1") (pintype "passive"))
      (node (ref "U7") (pin "1") (pinfunction "FSW_1") (pintype "passive"))
    )
    (net (code "46") (name "Net-(U7-ILIM)") (class "Default")
      (node (ref "R10") (pin "2") (pinfunction "2_2") (pintype "passive"))
      (node (ref "U7") (pin "8") (pinfunction "ILIM_8") (pintype "passive"))
    )
    (net (code "47") (name "Net-(U7-SW)") (class "Default")
      (node (ref "C15") (pin "2") (pinfunction "2_2") (pintype "passive"))
      (node (ref "L2") (pin "2") (pinfunction "2_2") (pintype "passive"))
      (node (ref "R6") (pin "2") (pinfunction "2_2") (pintype "passive"))
      (node (ref "U7") (pin "11") (pinfunction "SW_11") (pintype "passive"))
    )
    (net (code "48") (name "Net-(U7-VCC)") (class "Default")
      (node (ref "C20") (pin "2") (pinfunction "2_2") (pintype "passive"))
      (node (ref "U7") (pin "2") (pinfunction "VCC_2") (pintype "passive"))
    )
    (net (code "49") (name "VBAT") (class "Default")
      (node (ref "B1") (pin "1") (pinfunction "1_1") (pintype "passive"))
      (node (ref "B1") (pin "3") (pinfunction "3_3") (pintype "passive"))
      (node (ref "B1") (pin "5") (pinfunction "5_5") (pintype "passive"))
      (node (ref "C1") (pin "2") (pinfunction "2_2") (pintype "passive"))
      (node (ref "R11") (pin "2") (pinfunction "2_2") (pintype "passive"))
      (node (ref "U3") (pin "8") (pinfunction "BATT_8") (pintype "passive"))
      (node (ref "U8") (pin "1") (pinfunction "S_1") (pintype "passive"))
    )
    (net (code "50") (name "VBATo") (class "Default")
      (node (ref "C6") (pin "2") (pinfunction "2_2") (pintype "passive"))
      (node (ref "JP1") (pin "1") (pinfunction "C1_1") (pintype "passive"))
      (node (ref "L1") (pin "1") (pinfunction "1_1") (pintype "passive"))
      (node (ref "U1") (pin "3") (pinfunction "VIN_3") (pintype "passive"))
      (node (ref "U1") (pin "7") (pinfunction "EN_7") (pintype "passive"))
      (node (ref "U8") (pin "3") (pinfunction "D_3") (pintype "passive"))
    )
    (net (code "51") (name "VM") (class "Default")
      (node (ref "C7") (pin "2") (pinfunction "2_2") (pintype "passive"))
      (node (ref "C9") (pin "2") (pinfunction "2_2") (pintype "passive"))
      (node (ref "JP2") (pin "2") (pinfunction "C2_2") (pintype "passive"))
      (node (ref "JP3") (pin "2") (pinfunction "C2_2") (pintype "passive"))
      (node (ref "U4") (pin "1") (pinfunction "VM_1") (pintype "passive"))
      (node (ref "U5") (pin "1") (pinfunction "VM_1") (pintype "passive"))
    )
    (net (code "52") (name "VUSB") (class "Default")
      (node (ref "C2") (pin "2") (pinfunction "2_2") (pintype "passive"))
      (node (ref "J1") (pin "1") (pinfunction "VCC_1") (pintype "passive"))
      (node (ref "LED1") (pin "1") (pinfunction "A_1") (pintype "passive"))
      (node (ref "LED2") (pin "1") (pinfunction "A_1") (pintype "passive"))
      (node (ref "U3") (pin "1") (pinfunction "VIN_1") (pintype "passive"))
    )
    (net (code "53") (name "unconnected-(J1-D+-Pad3)") (class "Default")
      (node (ref "J1") (pin "3") (pinfunction "D+_3") (pintype "passive"))
    )
    (net (code "54") (name "unconnected-(J1-D--Pad2)") (class "Default")
      (node (ref "J1") (pin "2") (pinfunction "D-_2") (pintype "passive"))
    )
    (net (code "55") (name "unconnected-(J1-ID-Pad4)") (class "Default")
      (node (ref "J1") (pin "4") (pinfunction "ID_4") (pintype "passive"))
    )
    (net (code "56") (name "unconnected-(U2-ADC6-Pad19)") (class "Default")
      (node (ref "U2") (pin "19") (pinfunction "ADC6_19") (pintype "input"))
    )
    (net (code "57") (name "unconnected-(U2-ADC7-Pad22)") (class "Default")
      (node (ref "U2") (pin "22") (pinfunction "ADC7_22") (pintype "input"))
    )
    (net (code "58") (name "unconnected-(U3-~{FAST}-Pad6)") (class "Default")
      (node (ref "U3") (pin "6") (pinfunction "~{FAST}_6") (pintype "passive"))
    )
    (net (code "59") (name "unconnected-(U6-NC-Pad4)") (class "Default")
      (node (ref "U6") (pin "4") (pinfunction "NC_4") (pintype "passive"))
    )
  )
)
